# ESP32breakout_V2-send.net
KiCad netlist of a schematic drawn in EAGLE
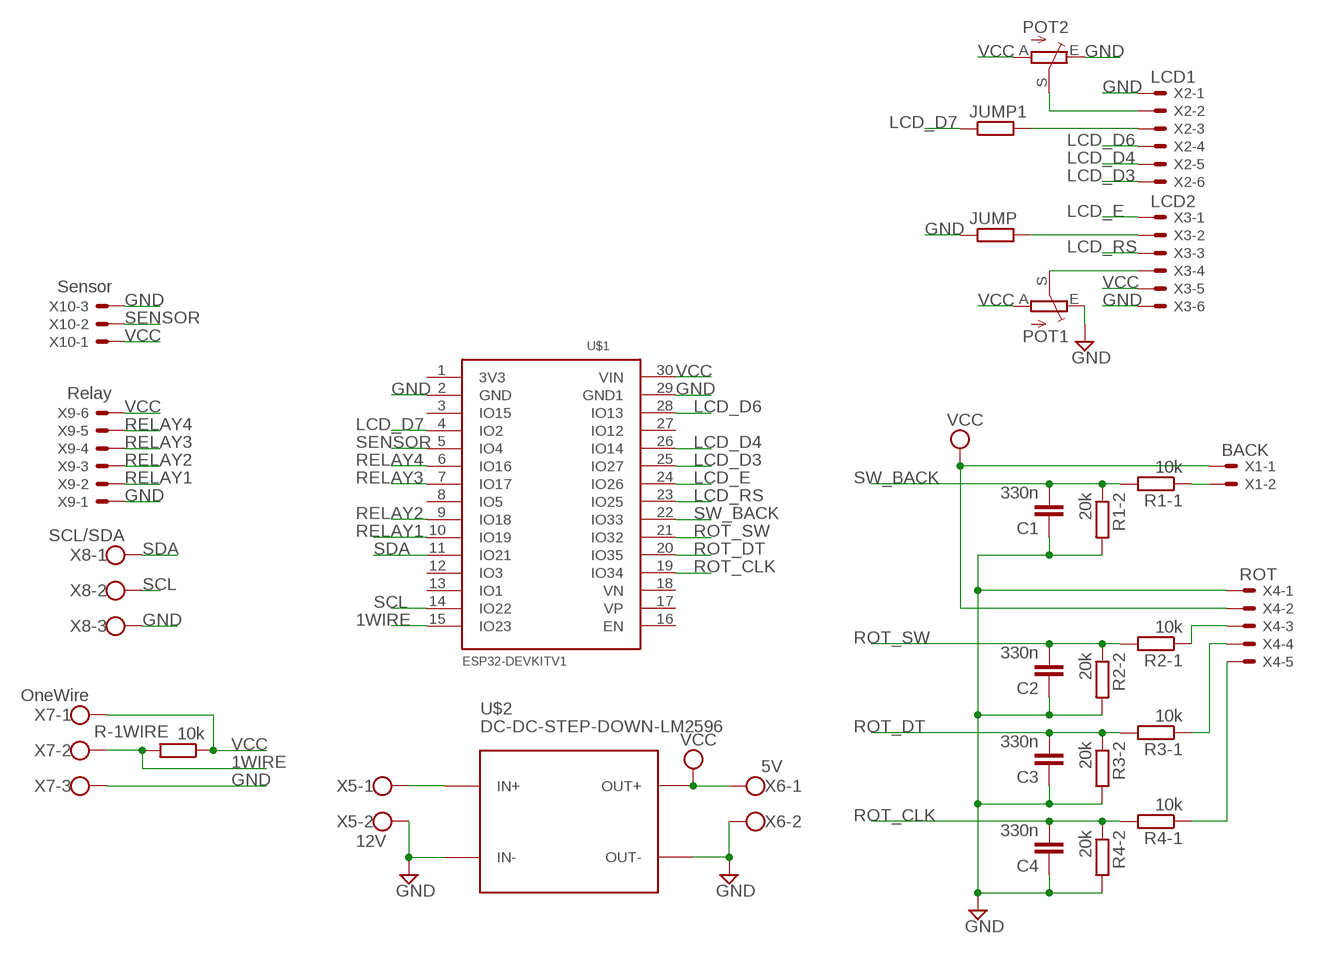
[diagram p0: schematic, sheet 1]

(export (version "E")
  (design (tool "Eeschema 10.0.6"))
  (components
    (comp (ref "C1")
      (value "330n")
      (footprint "eagle-import:C025-024X044")
      (libsource (lib "eagle-import") (part "C-EU025-024X044"))
    )
    (comp (ref "C2")
      (value "330n")
      (footprint "eagle-import:C025-024X044")
      (libsource (lib "eagle-import") (part "C-EU025-024X044"))
    )
    (comp (ref "C3")
      (value "330n")
      (footprint "eagle-import:C025-024X044")
      (libsource (lib "eagle-import") (part "C-EU025-024X044"))
    )
    (comp (ref "C4")
      (value "330n")
      (footprint "eagle-import:C025-024X044")
      (libsource (lib "eagle-import") (part "C-EU025-024X044"))
    )
    (comp (ref "JUMP")
      (value "R-EU_0207/5V")
      (footprint "eagle-import:0207_5V")
      (libsource (lib "eagle-import") (part "R-EU_0207/5V"))
    )
    (comp (ref "JUMP1")
      (value "R-EU_0207/5V")
      (footprint "eagle-import:0207_5V")
      (libsource (lib "eagle-import") (part "R-EU_0207/5V"))
    )
    (comp (ref "POT1")
      (value "TRIM_EU-CA6V")
      (footprint "eagle-import:CA6V")
      (libsource (lib "eagle-import") (part "TRIM_EU-CA6V"))
    )
    (comp (ref "POT2")
      (value "TRIM_EU-CA6V")
      (footprint "eagle-import:CA6V")
      (libsource (lib "eagle-import") (part "TRIM_EU-CA6V"))
    )
    (comp (ref "R-1WIRE")
      (value "10k")
      (footprint "eagle-import:0204_7")
      (libsource (lib "eagle-import") (part "R-EU_0204/7"))
    )
    (comp (ref "R1-1")
      (value "10k")
      (footprint "eagle-import:0204_7")
      (libsource (lib "eagle-import") (part "R-EU_0204/7"))
    )
    (comp (ref "R1-2")
      (value "20k")
      (footprint "eagle-import:0204_7")
      (libsource (lib "eagle-import") (part "R-EU_0204/7"))
    )
    (comp (ref "R2-1")
      (value "10k")
      (footprint "eagle-import:0204_7")
      (libsource (lib "eagle-import") (part "R-EU_0204/7"))
    )
    (comp (ref "R2-2")
      (value "20k")
      (footprint "eagle-import:0204_7")
      (libsource (lib "eagle-import") (part "R-EU_0204/7"))
    )
    (comp (ref "R3-1")
      (value "10k")
      (footprint "eagle-import:0204_7")
      (libsource (lib "eagle-import") (part "R-EU_0204/7"))
    )
    (comp (ref "R3-2")
      (value "20k")
      (footprint "eagle-import:0204_7")
      (libsource (lib "eagle-import") (part "R-EU_0204/7"))
    )
    (comp (ref "R4-1")
      (value "10k")
      (footprint "eagle-import:0204_7")
      (libsource (lib "eagle-import") (part "R-EU_0204/7"))
    )
    (comp (ref "R4-2")
      (value "20k")
      (footprint "eagle-import:0204_7")
      (libsource (lib "eagle-import") (part "R-EU_0204/7"))
    )
    (comp (ref "U$1")
      (value "ESP32DEVKITV1")
      (footprint "eagle-import:ESP32-DEVKITV1")
      (libsource (lib "eagle-import") (part "ESP32DEVKITV1"))
    )
    (comp (ref "U$2")
      (value "DC-DC-STEP-DOWN-LM2596")
      (footprint "eagle-import:DC-DC-STEP-DOWN-LM2596")
      (libsource (lib "eagle-import") (part "DC-DC-STEP-DOWN-LM2596"))
    )
    (comp (ref "X1")
      (value "BACK")
      (footprint "eagle-import:22-23-2021")
      (fields (field (name "MF") "MOLEX") (field (name "MPN") "22-23-2021"))
      (libsource (lib "eagle-import") (part "22-23-2021"))
    )
    (comp (ref "X2")
      (value "LCD1")
      (footprint "eagle-import:22-23-2061")
      (fields (field (name "MF") "MOLEX") (field (name "MPN") "22-23-2061"))
      (libsource (lib "eagle-import") (part "22-23-2061"))
    )
    (comp (ref "X3")
      (value "LCD2")
      (footprint "eagle-import:22-23-2061")
      (fields (field (name "MF") "MOLEX") (field (name "MPN") "22-23-2061"))
      (libsource (lib "eagle-import") (part "22-23-2061"))
    )
    (comp (ref "X4")
      (value "ROT")
      (footprint "eagle-import:22-23-2051")
      (fields (field (name "MF") "MOLEX") (field (name "MPN") "22-23-2051"))
      (libsource (lib "eagle-import") (part "22-23-2051"))
    )
    (comp (ref "X5")
      (value "12V")
      (footprint "eagle-import:W237-102")
      (fields (field (name "MPN") "237-102"))
      (libsource (lib "eagle-import") (part "W237-102"))
    )
    (comp (ref "X6")
      (value "5V")
      (footprint "eagle-import:W237-102")
      (fields (field (name "MPN") "237-102"))
      (libsource (lib "eagle-import") (part "W237-102"))
    )
    (comp (ref "X7")
      (value "OneWire")
      (footprint "eagle-import:W237-103")
      (fields (field (name "MPN") "237-103"))
      (libsource (lib "eagle-import") (part "W237-103"))
    )
    (comp (ref "X8")
      (value "SCL/SDA")
      (footprint "eagle-import:W237-103")
      (fields (field (name "MPN") "237-103"))
      (libsource (lib "eagle-import") (part "W237-103"))
    )
    (comp (ref "X9")
      (value "Relay")
      (footprint "eagle-import:22-23-2061")
      (fields (field (name "MF") "MOLEX") (field (name "MPN") "22-23-2061"))
      (libsource (lib "eagle-import") (part "22-23-2061"))
    )
    (comp (ref "X10")
      (value "Sensor")
      (footprint "eagle-import:22-23-2031")
      (fields (field (name "MF") "MOLEX") (field (name "MPN") "22-23-2031"))
      (libsource (lib "eagle-import") (part "22-23-2031"))
    )
  )
  (nets
    (net (code "1") (name "/1WIRE") (class "Default")
      (node (ref "R-1WIRE") (pin "2") (pinfunction "2_2") (pintype "passive"))
      (node (ref "U$1") (pin "15") (pinfunction "IO23_15") (pintype "bidirectional"))
      (node (ref "X7") (pin "2") (pinfunction "KL_2") (pintype "passive"))
    )
    (net (code "2") (name "/LCD_D3") (class "Default")
      (node (ref "U$1") (pin "25") (pinfunction "IO27_25") (pintype "bidirectional"))
      (node (ref "X2") (pin "6") (pinfunction "S_6") (pintype "passive"))
    )
    (net (code "3") (name "/LCD_D4") (class "Default")
      (node (ref "U$1") (pin "26") (pinfunction "IO14_26") (pintype "bidirectional"))
      (node (ref "X2") (pin "5") (pinfunction "S_5") (pintype "passive"))
    )
    (net (code "4") (name "/LCD_D6") (class "Default")
      (node (ref "U$1") (pin "28") (pinfunction "IO13_28") (pintype "bidirectional"))
      (node (ref "X2") (pin "4") (pinfunction "S_4") (pintype "passive"))
    )
    (net (code "5") (name "/LCD_D7") (class "Default")
      (node (ref "JUMP1") (pin "1") (pinfunction "1_1") (pintype "passive"))
      (node (ref "U$1") (pin "4") (pinfunction "IO2_4") (pintype "bidirectional"))
    )
    (net (code "6") (name "/LCD_E") (class "Default")
      (node (ref "U$1") (pin "24") (pinfunction "IO26_24") (pintype "bidirectional"))
      (node (ref "X3") (pin "1") (pinfunction "S_1") (pintype "passive"))
    )
    (net (code "7") (name "/LCD_RS") (class "Default")
      (node (ref "U$1") (pin "23") (pinfunction "IO25_23") (pintype "bidirectional"))
      (node (ref "X3") (pin "3") (pinfunction "S_3") (pintype "passive"))
    )
    (net (code "8") (name "/RELAY1") (class "Default")
      (node (ref "U$1") (pin "10") (pinfunction "IO19_10") (pintype "bidirectional"))
      (node (ref "X9") (pin "2") (pinfunction "S_2") (pintype "passive"))
    )
    (net (code "9") (name "/RELAY2") (class "Default")
      (node (ref "U$1") (pin "9") (pinfunction "IO18_9") (pintype "bidirectional"))
      (node (ref "X9") (pin "3") (pinfunction "S_3") (pintype "passive"))
    )
    (net (code "10") (name "/RELAY3") (class "Default")
      (node (ref "U$1") (pin "7") (pinfunction "IO17_7") (pintype "bidirectional"))
      (node (ref "X9") (pin "4") (pinfunction "S_4") (pintype "passive"))
    )
    (net (code "11") (name "/RELAY4") (class "Default")
      (node (ref "U$1") (pin "6") (pinfunction "IO16_6") (pintype "bidirectional"))
      (node (ref "X9") (pin "5") (pinfunction "S_5") (pintype "passive"))
    )
    (net (code "12") (name "/ROT_CLK") (class "Default")
      (node (ref "C4") (pin "2") (pinfunction "2_2") (pintype "passive"))
      (node (ref "R4-1") (pin "2") (pinfunction "2_2") (pintype "passive"))
      (node (ref "R4-2") (pin "1") (pinfunction "1_1") (pintype "passive"))
      (node (ref "U$1") (pin "19") (pinfunction "IO34_19") (pintype "bidirectional"))
    )
    (net (code "13") (name "/ROT_DT") (class "Default")
      (node (ref "C3") (pin "2") (pinfunction "2_2") (pintype "passive"))
      (node (ref "R3-1") (pin "2") (pinfunction "2_2") (pintype "passive"))
      (node (ref "R3-2") (pin "1") (pinfunction "1_1") (pintype "passive"))
      (node (ref "U$1") (pin "20") (pinfunction "IO35_20") (pintype "bidirectional"))
    )
    (net (code "14") (name "/ROT_SW") (class "Default")
      (node (ref "C2") (pin "2") (pinfunction "2_2") (pintype "passive"))
      (node (ref "R2-1") (pin "2") (pinfunction "2_2") (pintype "passive"))
      (node (ref "R2-2") (pin "1") (pinfunction "1_1") (pintype "passive"))
      (node (ref "U$1") (pin "21") (pinfunction "IO32_21") (pintype "bidirectional"))
    )
    (net (code "15") (name "/SCL") (class "Default")
      (node (ref "U$1") (pin "14") (pinfunction "IO22_14") (pintype "bidirectional"))
      (node (ref "X8") (pin "2") (pinfunction "KL_2") (pintype "passive"))
    )
    (net (code "16") (name "/SDA") (class "Default")
      (node (ref "U$1") (pin "11") (pinfunction "IO21_11") (pintype "bidirectional"))
      (node (ref "X8") (pin "1") (pinfunction "KL_1") (pintype "passive"))
    )
    (net (code "17") (name "/SENSOR") (class "Default")
      (node (ref "U$1") (pin "5") (pinfunction "IO4_5") (pintype "bidirectional"))
      (node (ref "X10") (pin "2") (pinfunction "S_2") (pintype "passive"))
    )
    (net (code "18") (name "/SW_BACK") (class "Default")
      (node (ref "C1") (pin "2") (pinfunction "2_2") (pintype "passive"))
      (node (ref "R1-1") (pin "2") (pinfunction "2_2") (pintype "passive"))
      (node (ref "R1-2") (pin "1") (pinfunction "1_1") (pintype "passive"))
      (node (ref "U$1") (pin "22") (pinfunction "IO33_22") (pintype "bidirectional"))
    )
    (net (code "19") (name "GND") (class "Default")
      (node (ref "C1") (pin "1") (pinfunction "1_1") (pintype "passive"))
      (node (ref "C2") (pin "1") (pinfunction "1_1") (pintype "passive"))
      (node (ref "C3") (pin "1") (pinfunction "1_1") (pintype "passive"))
      (node (ref "C4") (pin "1") (pinfunction "1_1") (pintype "passive"))
      (node (ref "JUMP") (pin "1") (pinfunction "1_1") (pintype "passive"))
      (node (ref "POT1") (pin "E") (pinfunction "E_E") (pintype "passive"))
      (node (ref "POT2") (pin "E") (pinfunction "E_E") (pintype "passive"))
      (node (ref "R1-2") (pin "2") (pinfunction "2_2") (pintype "passive"))
      (node (ref "R2-2") (pin "2") (pinfunction "2_2") (pintype "passive"))
      (node (ref "R3-2") (pin "2") (pinfunction "2_2") (pintype "passive"))
      (node (ref "R4-2") (pin "2") (pinfunction "2_2") (pintype "passive"))
      (node (ref "U$1") (pin "2") (pinfunction "GND_2") (pintype "bidirectional"))
      (node (ref "U$1") (pin "29") (pinfunction "GND1_29") (pintype "bidirectional"))
      (node (ref "U$2") (pin "IN-") (pinfunction "IN-_IN-") (pintype "bidirectional"))
      (node (ref "U$2") (pin "OUT-") (pinfunction "OUT-_OUT-") (pintype "bidirectional"))
      (node (ref "X10") (pin "3") (pinfunction "S_3") (pintype "passive"))
      (node (ref "X2") (pin "1") (pinfunction "S_1") (pintype "passive"))
      (node (ref "X3") (pin "6") (pinfunction "S_6") (pintype "passive"))
      (node (ref "X4") (pin "1") (pinfunction "S_1") (pintype "passive"))
      (node (ref "X5") (pin "2") (pinfunction "KL_2") (pintype "passive"))
      (node (ref "X6") (pin "2") (pinfunction "KL_2") (pintype "passive"))
      (node (ref "X7") (pin "3") (pinfunction "KL_3") (pintype "passive"))
      (node (ref "X8") (pin "3") (pinfunction "KL_3") (pintype "passive"))
      (node (ref "X9") (pin "1") (pinfunction "S_1") (pintype "passive"))
    )
    (net (code "20") (name "Net-(X1B-S)") (class "Default")
      (node (ref "R1-1") (pin "1") (pinfunction "1_1") (pintype "passive"))
      (node (ref "X1") (pin "2") (pinfunction "S_2") (pintype "passive"))
    )
    (net (code "21") (name "Net-(X2B-S)") (class "Default")
      (node (ref "POT2") (pin "S") (pinfunction "S_S") (pintype "passive"))
      (node (ref "X2") (pin "2") (pinfunction "S_2") (pintype "passive"))
    )
    (net (code "22") (name "Net-(X2C-S)") (class "Default")
      (node (ref "JUMP1") (pin "2") (pinfunction "2_2") (pintype "passive"))
      (node (ref "X2") (pin "3") (pinfunction "S_3") (pintype "passive"))
    )
    (net (code "23") (name "Net-(X3B-S)") (class "Default")
      (node (ref "JUMP") (pin "2") (pinfunction "2_2") (pintype "passive"))
      (node (ref "X3") (pin "2") (pinfunction "S_2") (pintype "passive"))
    )
    (net (code "24") (name "Net-(X3D-S)") (class "Default")
      (node (ref "POT1") (pin "S") (pinfunction "S_S") (pintype "passive"))
      (node (ref "X3") (pin "4") (pinfunction "S_4") (pintype "passive"))
    )
    (net (code "25") (name "Net-(X4C-S)") (class "Default")
      (node (ref "R2-1") (pin "1") (pinfunction "1_1") (pintype "passive"))
      (node (ref "X4") (pin "3") (pinfunction "S_3") (pintype "passive"))
    )
    (net (code "26") (name "Net-(X4D-S)") (class "Default")
      (node (ref "R3-1") (pin "1") (pinfunction "1_1") (pintype "passive"))
      (node (ref "X4") (pin "4") (pinfunction "S_4") (pintype "passive"))
    )
    (net (code "27") (name "Net-(X4E-S)") (class "Default")
      (node (ref "R4-1") (pin "1") (pinfunction "1_1") (pintype "passive"))
      (node (ref "X4") (pin "5") (pinfunction "S_5") (pintype "passive"))
    )
    (net (code "28") (name "Net-(X5A-KL)") (class "Default")
      (node (ref "U$2") (pin "IN+") (pinfunction "IN+_IN+") (pintype "bidirectional"))
      (node (ref "X5") (pin "1") (pinfunction "KL_1") (pintype "passive"))
    )
    (net (code "29") (name "VCC") (class "Default")
      (node (ref "POT1") (pin "A") (pinfunction "A_A") (pintype "passive"))
      (node (ref "POT2") (pin "A") (pinfunction "A_A") (pintype "passive"))
      (node (ref "R-1WIRE") (pin "1") (pinfunction "1_1") (pintype "passive"))
      (node (ref "U$1") (pin "30") (pinfunction "VIN_30") (pintype "bidirectional"))
      (node (ref "U$2") (pin "OUT+") (pinfunction "OUT+_OUT+") (pintype "bidirectional"))
      (node (ref "X1") (pin "1") (pinfunction "S_1") (pintype "passive"))
      (node (ref "X10") (pin "1") (pinfunction "S_1") (pintype "passive"))
      (node (ref "X3") (pin "5") (pinfunction "S_5") (pintype "passive"))
      (node (ref "X4") (pin "2") (pinfunction "S_2") (pintype "passive"))
      (node (ref "X6") (pin "1") (pinfunction "KL_1") (pintype "passive"))
      (node (ref "X7") (pin "1") (pinfunction "KL_1") (pintype "passive"))
      (node (ref "X9") (pin "6") (pinfunction "S_6") (pintype "passive"))
    )
    (net (code "30") (name "unconnected-(U$1-3V3-Pad1)") (class "Default")
      (node (ref "U$1") (pin "1") (pinfunction "3V3_1") (pintype "bidirectional"))
    )
    (net (code "31") (name "unconnected-(U$1-EN-Pad16)") (class "Default")
      (node (ref "U$1") (pin "16") (pinfunction "EN_16") (pintype "bidirectional"))
    )
    (net (code "32") (name "unconnected-(U$1-IO1-Pad13)") (class "Default")
      (node (ref "U$1") (pin "13") (pinfunction "IO1_13") (pintype "bidirectional"))
    )
    (net (code "33") (name "unconnected-(U$1-IO3-Pad12)") (class "Default")
      (node (ref "U$1") (pin "12") (pinfunction "IO3_12") (pintype "bidirectional"))
    )
    (net (code "34") (name "unconnected-(U$1-IO5-Pad8)") (class "Default")
      (node (ref "U$1") (pin "8") (pinfunction "IO5_8") (pintype "bidirectional"))
    )
    (net (code "35") (name "unconnected-(U$1-IO12-Pad27)") (class "Default")
      (node (ref "U$1") (pin "27") (pinfunction "IO12_27") (pintype "bidirectional"))
    )
    (net (code "36") (name "unconnected-(U$1-IO15-Pad3)") (class "Default")
      (node (ref "U$1") (pin "3") (pinfunction "IO15_3") (pintype "bidirectional"))
    )
    (net (code "37") (name "unconnected-(U$1-VN-Pad18)") (class "Default")
      (node (ref "U$1") (pin "18") (pinfunction "VN_18") (pintype "bidirectional"))
    )
    (net (code "38") (name "unconnected-(U$1-VP-Pad17)") (class "Default")
      (node (ref "U$1") (pin "17") (pinfunction "VP_17") (pintype "bidirectional"))
    )
  )
)
